# auto_switch_electric_bike_charger_schema.net
KiCad netlist of a schematic drawn in Altium Designer
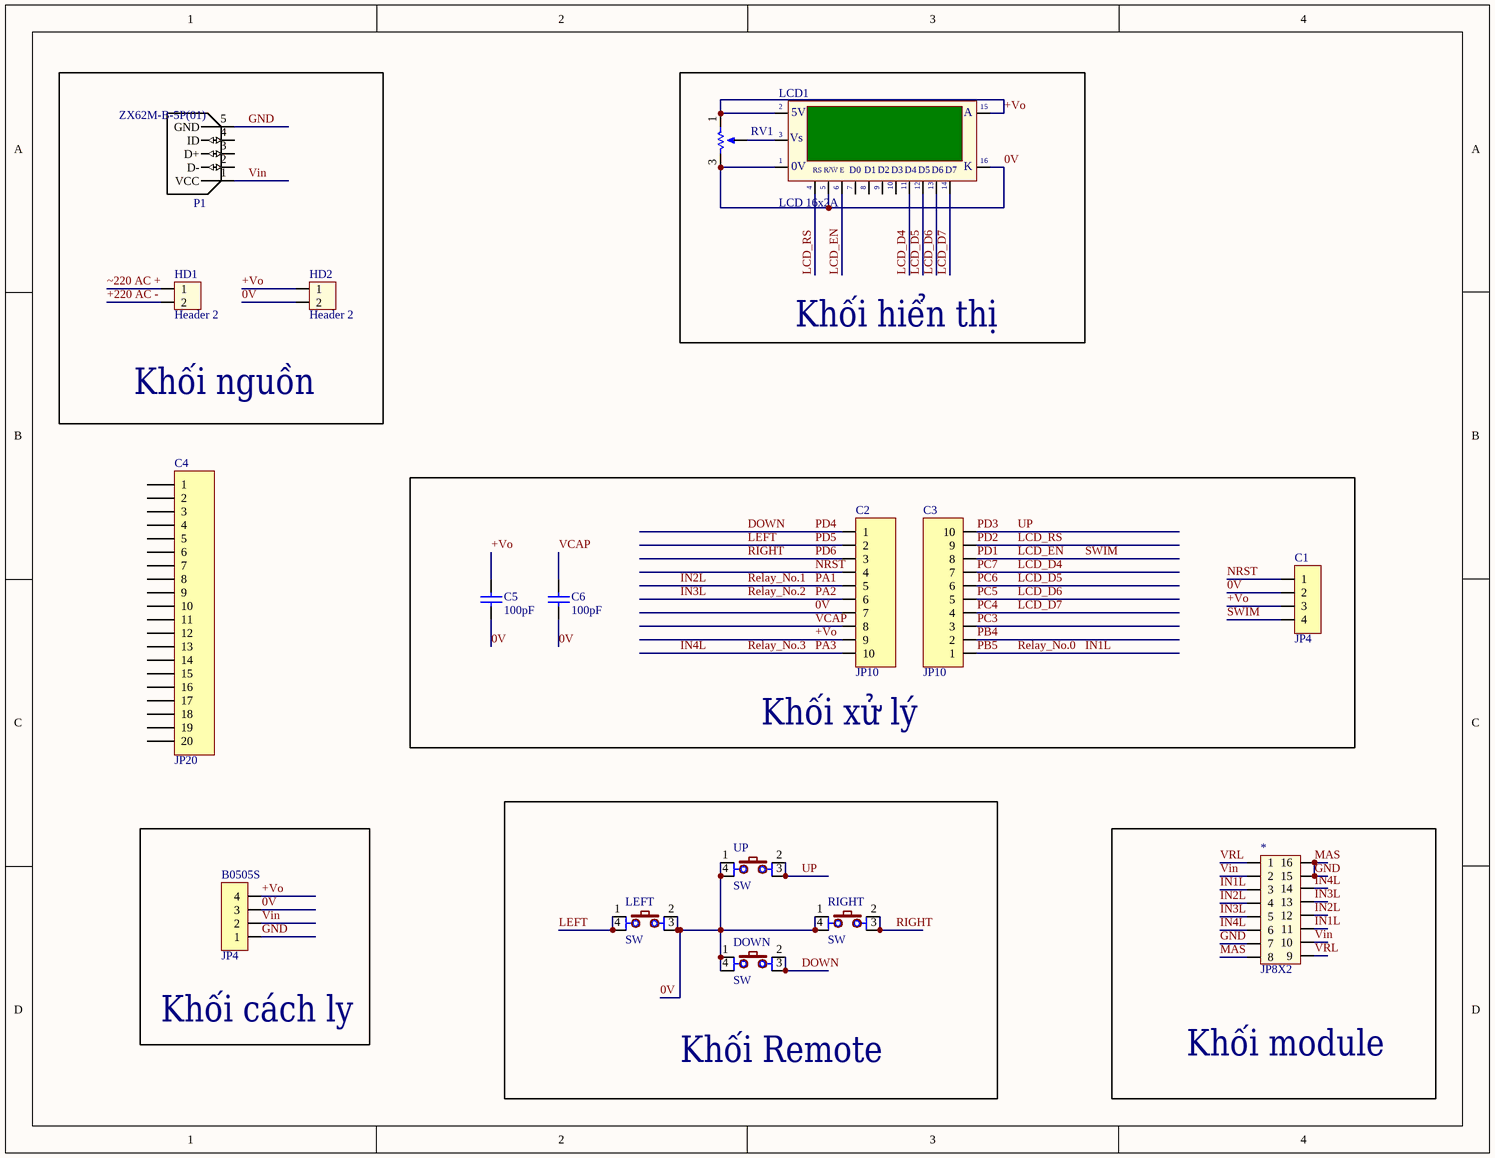
[diagram p0: auto switch electric bike charger_schematic.SchDoc]

(export (version "E")
  (design (tool "Eeschema 10.0.6"))
  (components
    (comp (ref "*") (value "JP8X2") (footprint "JP8X2") (libsource (lib "takahashi") (part "JP8X2")))
    (comp (ref "B0505S")
      (value "JP4")
      (footprint "JP4-C1T")
      (description "WR-PHD 2.54 mm Angled Socket Header")
      (fields
        (field (name "MANUFACTURER") "Würth Elektronik eiSos GmbH")
        (field (name "PARTNO") "613004143121")
        (field (name "CREATED BY") "Karrer Zheng")
      )
      (libsource (lib "My Library") (part "JP4"))
    )
    (comp (ref "C1")
      (value "JP4")
      (footprint "JP4-C1T")
      (description "WR-PHD 2.54 mm Angled Socket Header")
      (fields
        (field (name "MANUFACTURER") "Würth Elektronik eiSos GmbH")
        (field (name "PARTNO") "613004143121")
        (field (name "CREATED BY") "Karrer Zheng")
      )
      (libsource (lib "") (part "JP4_1"))
    )
    (comp (ref "C2")
      (value "JP10")
      (footprint "JP10-D1C")
      (description "WR-PHD 2.54 mm Angled Socket Header")
      (fields
        (field (name "MANUFACTURER") "Würth Elektronik eiSos GmbH")
        (field (name "PARTNO") "613010143121")
        (field (name "CREATED BY") "Karrer Zheng")
      )
      (libsource (lib "My Library") (part "JP10"))
    )
    (comp (ref "C3")
      (value "JP10")
      (footprint "JP10-D1C")
      (description "WR-PHD 2.54 mm Angled Socket Header")
      (fields
        (field (name "MANUFACTURER") "Würth Elektronik eiSos GmbH")
        (field (name "PARTNO") "613010143121")
        (field (name "CREATED BY") "Karrer Zheng")
      )
      (libsource (lib "") (part "JP10_1"))
    )
    (comp (ref "C4")
      (value "JP20")
      (footprint "JP20-D1T")
      (description "WR-PHD 2.54 mm Angled Socket Header")
      (fields
        (field (name "MANUFACTURER") "Würth Elektronik eiSos GmbH")
        (field (name "PARTNO") "613020143121")
        (field (name "CREATED BY") "Karrer Zheng")
      )
      (libsource (lib "ImetAltiumLibrary") (part "JP20"))
    )
    (comp (ref "C5")
      (value "100pF")
      (footprint "CN1")
      (description "Capacitor")
      (fields (field (name "Comment") "Cap Non-Pol"))
      (libsource (lib "PIF_Library") (part "Cap Non-Pol"))
    )
    (comp (ref "C6")
      (value "100pF")
      (footprint "CN1")
      (description "Capacitor")
      (fields (field (name "Comment") "Cap Non-Pol"))
      (libsource (lib "PIF_Library") (part "Cap Non-Pol"))
    )
    (comp (ref "DOWN")
      (value "SW")
      (footprint "SW2-DIP")
      (description "Switch button 4 pin")
      (libsource (lib "ImetAltiumLibrary") (part "SW4"))
    )
    (comp (ref "HD1")
      (value "Header 2")
      (footprint "HED2")
      (description "Header 2 (Green)")
      (libsource (lib "takahashi") (part "Hed2"))
    )
    (comp (ref "HD2")
      (value "Header 2")
      (footprint "HED2")
      (description "Header 2 (Green)")
      (libsource (lib "takahashi") (part "Hed2"))
    )
    (comp (ref "LCD1")
      (value "LCD 16x2A")
      (footprint "LCD16X2")
      (description "LCD dipslay 16 char, 2 line")
      (libsource (lib "My Library") (part "LCD16x2A"))
    )
    (comp (ref "LEFT")
      (value "SW")
      (footprint "SW2-DIP")
      (description "Switch button 4 pin")
      (libsource (lib "ImetAltiumLibrary") (part "SW4"))
    )
    (comp (ref "P1")
      (value "ZX62M-B-5P(01)")
      (footprint "HRS_ZX62M-B-5P(01)")
      (description "Conn Rcpt Micro Usb b Mid Mnt")
      (fields (field (name "MF") "Hirose") (field (name "MP") "ZX62M-B-5P"))
      (libsource (lib "Micro B USB Plug") (part "ZX62M-B-5P(01)"))
    )
    (comp (ref "RIGHT")
      (value "SW")
      (footprint "SW2-DIP")
      (description "Switch button 4 pin")
      (libsource (lib "ImetAltiumLibrary") (part "SW4"))
    )
    (comp (ref "RV1")
      (value "RV20K")
      (footprint "RVAR10K")
      (description "Variable Resistor")
      (fields (field (name "PUBLISHER") "Altium Limited"))
      (libsource (lib "My Library") (part "Variable Resistor"))
    )
    (comp (ref "UP")
      (value "SW")
      (footprint "SW2-DIP")
      (description "Switch button 4 pin")
      (libsource (lib "ImetAltiumLibrary") (part "SW4"))
    )
  )
  (nets
    (net (code "1") (name "/+220 AC -") (class "Default")
      (node (ref "HD1") (pin "2") (pinfunction "2_2") (pintype "passive"))
    )
    (net (code "2") (name "/+Vo") (class "Default")
      (node (ref "B0505S") (pin "4") (pinfunction "4_4") (pintype "passive"))
      (node (ref "C1") (pin "3") (pinfunction "3_3") (pintype "passive"))
      (node (ref "C2") (pin "9") (pinfunction "9_9") (pintype "passive"))
      (node (ref "C5") (pin "1") (pinfunction "1_1") (pintype "passive"))
      (node (ref "HD2") (pin "1") (pinfunction "1_1") (pintype "passive"))
      (node (ref "LCD1") (pin "15") (pinfunction "A_15") (pintype "passive"))
      (node (ref "LCD1") (pin "2") (pinfunction "VDD_2") (pintype "passive"))
      (node (ref "RV1") (pin "1") (pinfunction "1_1") (pintype "passive"))
    )
    (net (code "3") (name "/0V") (class "Default")
      (node (ref "B0505S") (pin "3") (pinfunction "3_3") (pintype "passive"))
      (node (ref "C1") (pin "2") (pinfunction "2_2") (pintype "passive"))
      (node (ref "C2") (pin "7") (pinfunction "7_7") (pintype "passive"))
      (node (ref "C5") (pin "2") (pinfunction "2_2") (pintype "passive"))
      (node (ref "C6") (pin "2") (pinfunction "2_2") (pintype "passive"))
      (node (ref "DOWN") (pin "1") (pintype "passive"))
      (node (ref "DOWN") (pin "4") (pinfunction "4_4") (pintype "passive"))
      (node (ref "HD2") (pin "2") (pinfunction "2_2") (pintype "passive"))
      (node (ref "LCD1") (pin "1") (pinfunction "GND_1") (pintype "passive"))
      (node (ref "LCD1") (pin "16") (pinfunction "K_16") (pintype "passive"))
      (node (ref "LCD1") (pin "5") (pinfunction "R/~{W}_5") (pintype "passive"))
      (node (ref "LEFT") (pin "2") (pinfunction "2_2") (pintype "passive"))
      (node (ref "LEFT") (pin "3") (pinfunction "3_3") (pintype "passive"))
      (node (ref "RIGHT") (pin "1") (pintype "passive"))
      (node (ref "RIGHT") (pin "4") (pinfunction "4_4") (pintype "passive"))
      (node (ref "RV1") (pin "3") (pinfunction "3_3") (pintype "passive"))
      (node (ref "UP") (pin "1") (pintype "passive"))
      (node (ref "UP") (pin "4") (pinfunction "4_4") (pintype "passive"))
    )
    (net (code "4") (name "/DOWN") (class "Default")
      (node (ref "C2") (pin "1") (pinfunction "1_1") (pintype "passive"))
      (node (ref "DOWN") (pin "2") (pinfunction "2_2") (pintype "passive"))
      (node (ref "DOWN") (pin "3") (pinfunction "3_3") (pintype "passive"))
    )
    (net (code "5") (name "/GND") (class "Default")
      (node (ref "*") (pin "15") (pinfunction "15_15") (pintype "passive"))
      (node (ref "*") (pin "16") (pinfunction "16_16") (pintype "passive"))
      (node (ref "*") (pin "7") (pinfunction "7_7") (pintype "passive"))
      (node (ref "*") (pin "8") (pinfunction "8_8") (pintype "passive"))
      (node (ref "B0505S") (pin "1") (pinfunction "1_1") (pintype "passive"))
      (node (ref "P1") (pin "5") (pinfunction "GND_5") (pintype "passive"))
    )
    (net (code "6") (name "/IN1L") (class "Default")
      (node (ref "*") (pin "11") (pinfunction "11_11") (pintype "passive"))
      (node (ref "*") (pin "3") (pinfunction "3_3") (pintype "passive"))
      (node (ref "C3") (pin "1") (pinfunction "1_1") (pintype "passive"))
    )
    (net (code "7") (name "/IN2L") (class "Default")
      (node (ref "*") (pin "12") (pinfunction "12_12") (pintype "passive"))
      (node (ref "*") (pin "4") (pinfunction "4_4") (pintype "passive"))
      (node (ref "C2") (pin "5") (pinfunction "5_5") (pintype "passive"))
    )
    (net (code "8") (name "/IN3L") (class "Default")
      (node (ref "*") (pin "13") (pinfunction "13_13") (pintype "passive"))
      (node (ref "*") (pin "5") (pinfunction "5_5") (pintype "passive"))
      (node (ref "C2") (pin "6") (pinfunction "6_6") (pintype "passive"))
    )
    (net (code "9") (name "/IN4L") (class "Default")
      (node (ref "*") (pin "14") (pinfunction "14_14") (pintype "passive"))
      (node (ref "*") (pin "6") (pinfunction "6_6") (pintype "passive"))
      (node (ref "C2") (pin "10") (pinfunction "10_10") (pintype "passive"))
    )
    (net (code "10") (name "/LCD_D4") (class "Default")
      (node (ref "C3") (pin "7") (pinfunction "7_7") (pintype "passive"))
      (node (ref "LCD1") (pin "11") (pinfunction "D4_11") (pintype "passive"))
    )
    (net (code "11") (name "/LCD_D5") (class "Default")
      (node (ref "C3") (pin "6") (pinfunction "6_6") (pintype "passive"))
      (node (ref "LCD1") (pin "12") (pinfunction "D5_12") (pintype "passive"))
    )
    (net (code "12") (name "/LCD_D6") (class "Default")
      (node (ref "C3") (pin "5") (pinfunction "5_5") (pintype "passive"))
      (node (ref "LCD1") (pin "13") (pinfunction "D6_13") (pintype "passive"))
    )
    (net (code "13") (name "/LCD_D7") (class "Default")
      (node (ref "C3") (pin "4") (pinfunction "4_4") (pintype "passive"))
      (node (ref "LCD1") (pin "14") (pinfunction "D7_14") (pintype "passive"))
    )
    (net (code "14") (name "/LCD_EN") (class "Default")
      (node (ref "C1") (pin "4") (pinfunction "4_4") (pintype "passive"))
      (node (ref "C3") (pin "8") (pinfunction "8_8") (pintype "passive"))
      (node (ref "LCD1") (pin "6") (pinfunction "~{EN}_6") (pintype "passive"))
    )
    (net (code "15") (name "/LCD_RS") (class "Default")
      (node (ref "C3") (pin "9") (pinfunction "9_9") (pintype "passive"))
      (node (ref "LCD1") (pin "4") (pinfunction "RS_4") (pintype "passive"))
    )
    (net (code "16") (name "/LEFT") (class "Default")
      (node (ref "C2") (pin "2") (pinfunction "2_2") (pintype "passive"))
      (node (ref "LEFT") (pin "1") (pintype "passive"))
      (node (ref "LEFT") (pin "4") (pinfunction "4_4") (pintype "passive"))
    )
    (net (code "17") (name "/NRST") (class "Default")
      (node (ref "C1") (pin "1") (pinfunction "1_1") (pintype "passive"))
      (node (ref "C2") (pin "4") (pinfunction "4_4") (pintype "passive"))
    )
    (net (code "18") (name "/PB4") (class "Default")
      (node (ref "C3") (pin "2") (pinfunction "2_2") (pintype "passive"))
    )
    (net (code "19") (name "/PC3") (class "Default")
      (node (ref "C3") (pin "3") (pinfunction "3_3") (pintype "passive"))
    )
    (net (code "20") (name "/PD3") (class "Default")
      (node (ref "C3") (pin "10") (pinfunction "10_10") (pintype "passive"))
      (node (ref "UP") (pin "2") (pinfunction "2_2") (pintype "passive"))
      (node (ref "UP") (pin "3") (pinfunction "3_3") (pintype "passive"))
    )
    (net (code "21") (name "/PD6") (class "Default")
      (node (ref "C2") (pin "3") (pinfunction "3_3") (pintype "passive"))
      (node (ref "RIGHT") (pin "2") (pinfunction "2_2") (pintype "passive"))
      (node (ref "RIGHT") (pin "3") (pinfunction "3_3") (pintype "passive"))
    )
    (net (code "22") (name "/VCAP") (class "Default")
      (node (ref "C2") (pin "8") (pinfunction "8_8") (pintype "passive"))
      (node (ref "C6") (pin "1") (pinfunction "1_1") (pintype "passive"))
    )
    (net (code "23") (name "/VRL") (class "Default")
      (node (ref "*") (pin "1") (pinfunction "1_1") (pintype "passive"))
      (node (ref "*") (pin "9") (pinfunction "9_9") (pintype "passive"))
    )
    (net (code "24") (name "/Vin") (class "Default")
      (node (ref "*") (pin "10") (pinfunction "10_10") (pintype "passive"))
      (node (ref "*") (pin "2") (pinfunction "2_2") (pintype "passive"))
      (node (ref "B0505S") (pin "2") (pinfunction "2_2") (pintype "passive"))
      (node (ref "P1") (pin "1") (pinfunction "VCC_1") (pintype "power_in"))
    )
    (net (code "25") (name "/~220 AC +") (class "Default")
      (node (ref "HD1") (pin "1") (pinfunction "1_1") (pintype "passive"))
    )
    (net (code "26") (name "Net-(LCD1-VEE)") (class "Default")
      (node (ref "LCD1") (pin "3") (pinfunction "VEE_3") (pintype "passive"))
      (node (ref "RV1") (pin "2") (pinfunction "2_2") (pintype "passive"))
    )
    (net (code "27") (name "unconnected-(C4-Pad1)") (class "Default")
      (node (ref "C4") (pin "1") (pinfunction "1_1") (pintype "passive"))
    )
    (net (code "28") (name "unconnected-(C4-Pad2)") (class "Default")
      (node (ref "C4") (pin "2") (pinfunction "2_2") (pintype "passive"))
    )
    (net (code "29") (name "unconnected-(C4-Pad3)") (class "Default")
      (node (ref "C4") (pin "3") (pinfunction "3_3") (pintype "passive"))
    )
    (net (code "30") (name "unconnected-(C4-Pad4)") (class "Default")
      (node (ref "C4") (pin "4") (pinfunction "4_4") (pintype "passive"))
    )
    (net (code "31") (name "unconnected-(C4-Pad5)") (class "Default")
      (node (ref "C4") (pin "5") (pinfunction "5_5") (pintype "passive"))
    )
    (net (code "32") (name "unconnected-(C4-Pad6)") (class "Default")
      (node (ref "C4") (pin "6") (pinfunction "6_6") (pintype "passive"))
    )
    (net (code "33") (name "unconnected-(C4-Pad7)") (class "Default")
      (node (ref "C4") (pin "7") (pinfunction "7_7") (pintype "passive"))
    )
    (net (code "34") (name "unconnected-(C4-Pad8)") (class "Default")
      (node (ref "C4") (pin "8") (pinfunction "8_8") (pintype "passive"))
    )
    (net (code "35") (name "unconnected-(C4-Pad9)") (class "Default")
      (node (ref "C4") (pin "9") (pinfunction "9_9") (pintype "passive"))
    )
    (net (code "36") (name "unconnected-(C4-Pad10)") (class "Default")
      (node (ref "C4") (pin "10") (pinfunction "10_10") (pintype "passive"))
    )
    (net (code "37") (name "unconnected-(C4-Pad11)") (class "Default")
      (node (ref "C4") (pin "11") (pinfunction "11_11") (pintype "passive"))
    )
    (net (code "38") (name "unconnected-(C4-Pad12)") (class "Default")
      (node (ref "C4") (pin "12") (pinfunction "12_12") (pintype "passive"))
    )
    (net (code "39") (name "unconnected-(C4-Pad13)") (class "Default")
      (node (ref "C4") (pin "13") (pinfunction "13_13") (pintype "passive"))
    )
    (net (code "40") (name "unconnected-(C4-Pad14)") (class "Default")
      (node (ref "C4") (pin "14") (pinfunction "14_14") (pintype "passive"))
    )
    (net (code "41") (name "unconnected-(C4-Pad15)") (class "Default")
      (node (ref "C4") (pin "15") (pinfunction "15_15") (pintype "passive"))
    )
    (net (code "42") (name "unconnected-(C4-Pad16)") (class "Default")
      (node (ref "C4") (pin "16") (pinfunction "16_16") (pintype "passive"))
    )
    (net (code "43") (name "unconnected-(C4-Pad17)") (class "Default")
      (node (ref "C4") (pin "17") (pinfunction "17_17") (pintype "passive"))
    )
    (net (code "44") (name "unconnected-(C4-Pad18)") (class "Default")
      (node (ref "C4") (pin "18") (pinfunction "18_18") (pintype "passive"))
    )
    (net (code "45") (name "unconnected-(C4-Pad19)") (class "Default")
      (node (ref "C4") (pin "19") (pinfunction "19_19") (pintype "passive"))
    )
    (net (code "46") (name "unconnected-(C4-Pad20)") (class "Default")
      (node (ref "C4") (pin "20") (pinfunction "20_20") (pintype "passive"))
    )
    (net (code "47") (name "unconnected-(LCD1-D0-Pad7)") (class "Default")
      (node (ref "LCD1") (pin "7") (pinfunction "D0_7") (pintype "passive"))
    )
    (net (code "48") (name "unconnected-(LCD1-D1-Pad8)") (class "Default")
      (node (ref "LCD1") (pin "8") (pinfunction "D1_8") (pintype "passive"))
    )
    (net (code "49") (name "unconnected-(LCD1-D2-Pad9)") (class "Default")
      (node (ref "LCD1") (pin "9") (pinfunction "D2_9") (pintype "passive"))
    )
    (net (code "50") (name "unconnected-(LCD1-D3-Pad10)") (class "Default")
      (node (ref "LCD1") (pin "10") (pinfunction "D3_10") (pintype "passive"))
    )
    (net (code "51") (name "unconnected-(P1-D+-Pad3)") (class "Default")
      (node (ref "P1") (pin "3") (pinfunction "D+_3") (pintype "bidirectional"))
    )
    (net (code "52") (name "unconnected-(P1-D--Pad2)") (class "Default")
      (node (ref "P1") (pin "2") (pinfunction "D-_2") (pintype "bidirectional"))
    )
    (net (code "53") (name "unconnected-(P1-ID-Pad4)") (class "Default")
      (node (ref "P1") (pin "4") (pinfunction "ID_4") (pintype "bidirectional"))
    )
  )
)
